# Power_Supply.net
KiCad netlist of a schematic drawn in Altium Designer
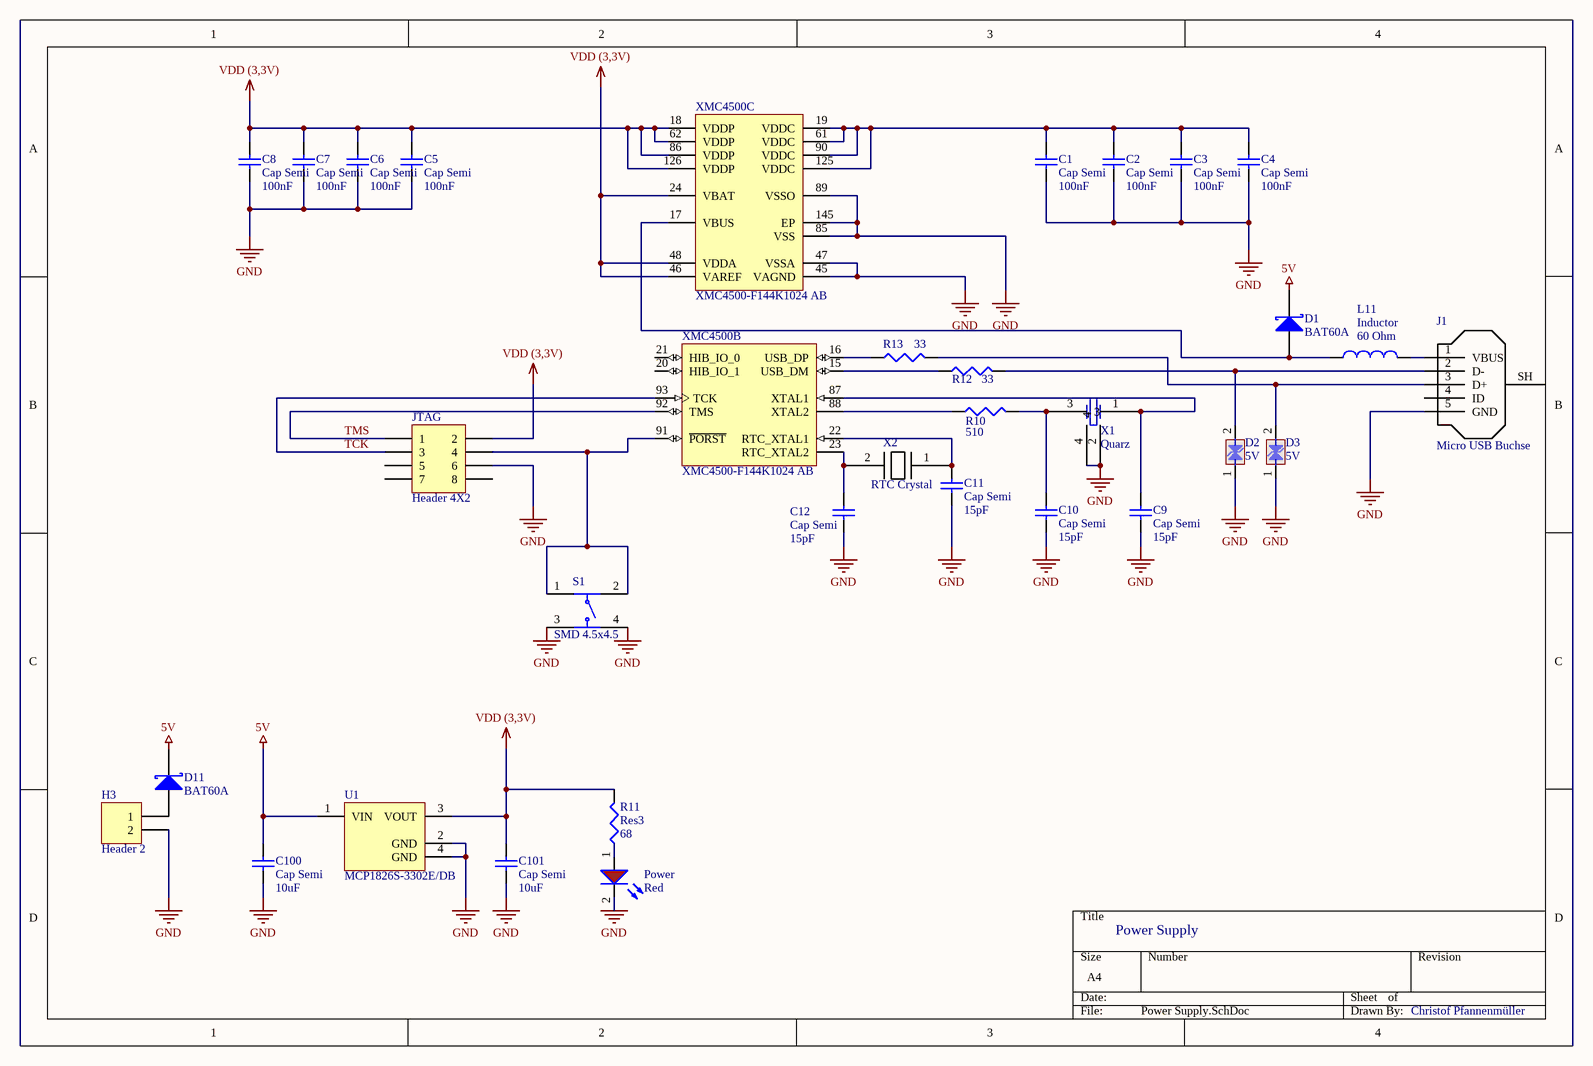
[diagram p0: Power Supply.SchDoc]

(export (version "E")
  (design (tool "Eeschema 10.0.6"))
  (components
    (comp (ref "C1")
      (value "Cap Semi")
      (footprint "0402")
      (description "Capacitor (Semiconductor SIM Model)")
      (fields (field (name "ALTIUM_VALUE") "100nF") (field (name "PUBLISHER") "Altium Limited"))
      (libsource (lib "Miscellaneous Devices") (part "Cap Semi"))
    )
    (comp (ref "C2")
      (value "Cap Semi")
      (footprint "0402")
      (description "Capacitor (Semiconductor SIM Model)")
      (fields (field (name "ALTIUM_VALUE") "100nF") (field (name "PUBLISHER") "Altium Limited"))
      (libsource (lib "Miscellaneous Devices") (part "Cap Semi"))
    )
    (comp (ref "C3")
      (value "Cap Semi")
      (footprint "0402")
      (description "Capacitor (Semiconductor SIM Model)")
      (fields (field (name "ALTIUM_VALUE") "100nF") (field (name "PUBLISHER") "Altium Limited"))
      (libsource (lib "Miscellaneous Devices") (part "Cap Semi"))
    )
    (comp (ref "C4")
      (value "Cap Semi")
      (footprint "0402")
      (description "Capacitor (Semiconductor SIM Model)")
      (fields (field (name "ALTIUM_VALUE") "100nF") (field (name "PUBLISHER") "Altium Limited"))
      (libsource (lib "Miscellaneous Devices") (part "Cap Semi"))
    )
    (comp (ref "C5")
      (value "Cap Semi")
      (footprint "0402")
      (description "Capacitor (Semiconductor SIM Model)")
      (fields (field (name "ALTIUM_VALUE") "100nF") (field (name "PUBLISHER") "Altium Limited"))
      (libsource (lib "Miscellaneous Devices") (part "Cap Semi"))
    )
    (comp (ref "C6")
      (value "Cap Semi")
      (footprint "0402")
      (description "Capacitor (Semiconductor SIM Model)")
      (fields (field (name "ALTIUM_VALUE") "100nF") (field (name "PUBLISHER") "Altium Limited"))
      (libsource (lib "Miscellaneous Devices") (part "Cap Semi"))
    )
    (comp (ref "C7")
      (value "Cap Semi")
      (footprint "0402")
      (description "Capacitor (Semiconductor SIM Model)")
      (fields (field (name "ALTIUM_VALUE") "100nF") (field (name "PUBLISHER") "Altium Limited"))
      (libsource (lib "Miscellaneous Devices") (part "Cap Semi"))
    )
    (comp (ref "C8")
      (value "Cap Semi")
      (footprint "0402")
      (description "Capacitor (Semiconductor SIM Model)")
      (fields (field (name "ALTIUM_VALUE") "100nF") (field (name "PUBLISHER") "Altium Limited"))
      (libsource (lib "Miscellaneous Devices") (part "Cap Semi"))
    )
    (comp (ref "C9")
      (value "Cap Semi")
      (footprint "0402")
      (description "Capacitor (Semiconductor SIM Model)")
      (fields (field (name "ALTIUM_VALUE") "15pF") (field (name "PUBLISHER") "Altium Limited"))
      (libsource (lib "Miscellaneous Devices") (part "Cap Semi"))
    )
    (comp (ref "C10")
      (value "Cap Semi")
      (footprint "0402")
      (description "Capacitor (Semiconductor SIM Model)")
      (fields (field (name "ALTIUM_VALUE") "15pF") (field (name "PUBLISHER") "Altium Limited"))
      (libsource (lib "Miscellaneous Devices") (part "Cap Semi"))
    )
    (comp (ref "C11")
      (value "Cap Semi")
      (footprint "0402")
      (description "Capacitor (Semiconductor SIM Model)")
      (fields (field (name "ALTIUM_VALUE") "15pF") (field (name "PUBLISHER") "Altium Limited"))
      (libsource (lib "Miscellaneous Devices") (part "Cap Semi"))
    )
    (comp (ref "C12")
      (value "Cap Semi")
      (footprint "0402")
      (description "Capacitor (Semiconductor SIM Model)")
      (fields (field (name "ALTIUM_VALUE") "15pF") (field (name "PUBLISHER") "Altium Limited"))
      (libsource (lib "Miscellaneous Devices") (part "Cap Semi"))
    )
    (comp (ref "C100")
      (value "Cap Semi")
      (footprint "C1206")
      (description "Capacitor (Semiconductor SIM Model)")
      (fields (field (name "ALTIUM_VALUE") "10uF") (field (name "PUBLISHER") "Altium Limited"))
      (libsource (lib "Miscellaneous Devices") (part "Cap Semi"))
    )
    (comp (ref "C101")
      (value "Cap Semi")
      (footprint "C1206")
      (description "Capacitor (Semiconductor SIM Model)")
      (fields (field (name "ALTIUM_VALUE") "10uF") (field (name "PUBLISHER") "Altium Limited"))
      (libsource (lib "Miscellaneous Devices") (part "Cap Semi"))
    )
    (comp (ref "D1")
      (value "BAT60A")
      (footprint "SOD-323")
      (description "Silicon AF Schottky Rectifier Diode with Extreme Low VF Drop")
      (fields (field (name "PUBLISHER") "Altium Limited"))
      (libsource (lib "Infineon Discrete Diode") (part "BAT60A"))
    )
    (comp (ref "D2")
      (value "5V")
      (footprint "WE-VE_0603")
      (description "WE-VE ESD Suppressor, 0603, VDC=5V")
      (fields
        (field (name "PARTNO") "82356050560")
        (field (name "MANUFACTURER") "Wurth Elektronik")
        (field (name "CREATED BY") "BJ.Chen")
      )
      (libsource (lib "WE-VE_rev16a") (part "WE-VE 0603, 82356050560"))
    )
    (comp (ref "D3")
      (value "5V")
      (footprint "WE-VE_0603")
      (description "WE-VE ESD Suppressor, 0603, VDC=5V")
      (fields
        (field (name "PARTNO") "82356050560")
        (field (name "MANUFACTURER") "Wurth Elektronik")
        (field (name "CREATED BY") "BJ.Chen")
      )
      (libsource (lib "WE-VE_rev16a") (part "WE-VE 0603, 82356050560"))
    )
    (comp (ref "D11")
      (value "BAT60A")
      (footprint "SOD-323")
      (description "Silicon AF Schottky Rectifier Diode with Extreme Low VF Drop")
      (fields (field (name "PUBLISHER") "Altium Limited"))
      (libsource (lib "Infineon Discrete Diode") (part "BAT60A"))
    )
    (comp (ref "H3")
      (value "Header 2")
      (footprint "HDR1X2")
      (description "Header, 2-Pin")
      (fields (field (name "PUBLISHER") "Altium Limited"))
      (libsource (lib "Miscellaneous Connectors") (part "Header 2"))
    )
    (comp (ref "J1")
      (value "Micro USB Buchse")
      (footprint "Micro USB Buchse - Molex")
      (libsource (lib "Schematic library") (part "Micro USB Buchse - Molex"))
    )
    (comp (ref "JTAG")
      (value "Header 4X2")
      (footprint "HDR2X4")
      (description "Header, 4-Pin, Dual row")
      (fields (field (name "PUBLISHER") "Altium Limited"))
      (libsource (lib "Miscellaneous Connectors") (part "Header 4X2"))
    )
    (comp (ref "L11")
      (value "Inductor")
      (footprint "0603")
      (fields (field (name "ALTIUM_VALUE") "60 Ohm") (field (name "PUBLISHER") "Altium Limited"))
      (libsource (lib "Miscellaneous Devices") (part "Inductor"))
    )
    (comp (ref "Power")
      (value "Red")
      (footprint "LED_0805_Red")
      (description "SMD mono-color Chip LED, WL-SMCW, Red")
      (fields
        (field (name "PARTNO") "150080RS75000")
        (field (name "MANUFACTURER") "W黵th Elektronik eiSos GmbH")
        (field (name "CREATED BY") "Christin Otto")
      )
      (libsource (lib "WL-SMCW_rev15b") (part "WL-SMCW 0805  150080RS75000"))
    )
    (comp (ref "R10")
      (value "510")
      (footprint "J1-0603")
      (description "Resistor")
      (fields (field (name "Comment") "Res3") (field (name "PUBLISHER") "Altium Limited"))
      (libsource (lib "Miscellaneous Devices") (part "Res3"))
    )
    (comp (ref "R11")
      (value "Res3")
      (footprint "J1-0603")
      (description "Resistor")
      (fields (field (name "ALTIUM_VALUE") "68") (field (name "PUBLISHER") "Altium Limited"))
      (libsource (lib "Miscellaneous Devices") (part "Res3"))
    )
    (comp (ref "R12")
      (value "33")
      (footprint "J1-0603")
      (description "Resistor")
      (fields (field (name "Comment") "Res3") (field (name "PUBLISHER") "Altium Limited"))
      (libsource (lib "Miscellaneous Devices") (part "Res3"))
    )
    (comp (ref "R13")
      (value "33")
      (footprint "J1-0603")
      (description "Resistor")
      (fields (field (name "Comment") "Res3") (field (name "PUBLISHER") "Altium Limited"))
      (libsource (lib "Miscellaneous Devices") (part "Res3"))
    )
    (comp (ref "S1")
      (value "SMD 4.5x4.5")
      (footprint "430181038816")
      (description "WS-TASV 4.5x4.5 mm SMD")
      (fields
        (field (name "PARTNO") "430181038816")
        (field (name "MANUFACTURER") "Wurth Elektronik")
        (field (name "CREATED BY") "Baojun Chen")
      )
      (libsource (lib "WS-TASV_rev15a") (part "WS-TASV, 430181038816"))
    )
    (comp (ref "U1")
      (value "MCP1826S-3302E/DB")
      (footprint "SOT-223-DB3_N")
      (description "1000 mA, Low Voltage, Low Quiescent Current LDO Regulator, 3-Pin SOT-223, Extended Temperature")
      (fields (field (name "MANUFACTURER") "Microchip"))
      (libsource (lib "Microchip Power Management Line Regulator") (part "MCP1826S-3302E/DB"))
    )
    (comp (ref "X1") (value "Quarz") (footprint "Quarz") (libsource (lib "Schlib1") (part "Quarz")))
    (comp (ref "X2")
      (value "RTC Crystal")
      (footprint "RTC Uhrenquarz  1.5x3.2 SMD")
      (libsource (lib "Schematic library") (part "RTC Crystal"))
    )
    (comp (ref "XMC4500")
      (value "XMC4500-F144K1024 AB")
      (footprint "INF-PG-LQFP-144-18-6500X6500TP_N")
      (fields (field (name "MANUFACTURER") "Infineon"))
      (libsource (lib "Infineon XMC4000") (part "XMC4500-F144K1024 AB"))
    )
  )
  (nets
    (net (code "1") (name "/TCK") (class "Default")
      (node (ref "JTAG") (pin "3") (pinfunction "3_3") (pintype "passive"))
      (node (ref "XMC4500") (pin "93") (pinfunction "TCK_93") (pintype "input"))
    )
    (net (code "2") (name "/TMS") (class "Default")
      (node (ref "JTAG") (pin "1") (pinfunction "1_1") (pintype "passive"))
      (node (ref "XMC4500") (pin "92") (pinfunction "TMS_92") (pintype "bidirectional"))
    )
    (net (code "3") (name "5V") (class "Default")
      (node (ref "C100") (pin "2") (pinfunction "2_2") (pintype "passive"))
      (node (ref "D1") (pin "1") (pinfunction "K_1") (pintype "passive"))
      (node (ref "D11") (pin "1") (pinfunction "K_1") (pintype "passive"))
      (node (ref "U1") (pin "1") (pinfunction "VIN_1") (pintype "power_in"))
    )
    (net (code "4") (name "GND") (class "Default")
      (node (ref "C1") (pin "1") (pinfunction "1_1") (pintype "passive"))
      (node (ref "C10") (pin "1") (pinfunction "1_1") (pintype "passive"))
      (node (ref "C100") (pin "1") (pinfunction "1_1") (pintype "passive"))
      (node (ref "C101") (pin "1") (pinfunction "1_1") (pintype "passive"))
      (node (ref "C11") (pin "1") (pinfunction "1_1") (pintype "passive"))
      (node (ref "C12") (pin "1") (pinfunction "1_1") (pintype "passive"))
      (node (ref "C2") (pin "1") (pinfunction "1_1") (pintype "passive"))
      (node (ref "C3") (pin "1") (pinfunction "1_1") (pintype "passive"))
      (node (ref "C4") (pin "1") (pinfunction "1_1") (pintype "passive"))
      (node (ref "C5") (pin "1") (pinfunction "1_1") (pintype "passive"))
      (node (ref "C6") (pin "1") (pinfunction "1_1") (pintype "passive"))
      (node (ref "C7") (pin "1") (pinfunction "1_1") (pintype "passive"))
      (node (ref "C8") (pin "1") (pinfunction "1_1") (pintype "passive"))
      (node (ref "C9") (pin "1") (pinfunction "1_1") (pintype "passive"))
      (node (ref "D2") (pin "1") (pinfunction "I/O1_1") (pintype "passive"))
      (node (ref "D3") (pin "1") (pinfunction "I/O1_1") (pintype "passive"))
      (node (ref "H3") (pin "2") (pinfunction "2_2") (pintype "passive"))
      (node (ref "J1") (pin "5") (pinfunction "GND_5") (pintype "passive"))
      (node (ref "JTAG") (pin "6") (pinfunction "6_6") (pintype "passive"))
      (node (ref "Power") (pin "2") (pinfunction "C_2") (pintype "passive"))
      (node (ref "S1") (pin "3") (pinfunction "3_3") (pintype "passive"))
      (node (ref "S1") (pin "4") (pinfunction "4_4") (pintype "passive"))
      (node (ref "U1") (pin "2") (pinfunction "GND_2") (pintype "power_in"))
      (node (ref "U1") (pin "4") (pinfunction "GND_4") (pintype "power_in"))
      (node (ref "X1") (pin "2") (pinfunction "2_2") (pintype "passive"))
      (node (ref "X1") (pin "4") (pinfunction "4_4") (pintype "passive"))
      (node (ref "XMC4500") (pin "145") (pinfunction "EP_145") (pintype "power_in"))
      (node (ref "XMC4500") (pin "45") (pinfunction "VAGND_45") (pintype "power_in"))
      (node (ref "XMC4500") (pin "47") (pinfunction "VSSA_47") (pintype "power_in"))
      (node (ref "XMC4500") (pin "85") (pinfunction "VSS_85") (pintype "power_in"))
      (node (ref "XMC4500") (pin "89") (pinfunction "VSSO_89") (pintype "power_in"))
    )
    (net (code "5") (name "Net-(C1-Pad2)") (class "Default")
      (node (ref "C1") (pin "2") (pinfunction "2_2") (pintype "passive"))
      (node (ref "C2") (pin "2") (pinfunction "2_2") (pintype "passive"))
      (node (ref "C3") (pin "2") (pinfunction "2_2") (pintype "passive"))
      (node (ref "C4") (pin "2") (pinfunction "2_2") (pintype "passive"))
      (node (ref "XMC4500") (pin "125") (pinfunction "VDDC_125") (pintype "power_in"))
      (node (ref "XMC4500") (pin "19") (pinfunction "VDDC_19") (pintype "power_in"))
      (node (ref "XMC4500") (pin "61") (pinfunction "VDDC_61") (pintype "power_in"))
      (node (ref "XMC4500") (pin "90") (pinfunction "VDDC_90") (pintype "power_in"))
    )
    (net (code "6") (name "Net-(C10-Pad2)") (class "Default")
      (node (ref "C10") (pin "2") (pinfunction "2_2") (pintype "passive"))
      (node (ref "R10") (pin "2") (pinfunction "2_2") (pintype "passive"))
      (node (ref "X1") (pin "3") (pinfunction "3_3") (pintype "passive"))
    )
    (net (code "7") (name "Net-(D1-A)") (class "Default")
      (node (ref "D1") (pin "2") (pinfunction "A_2") (pintype "passive"))
      (node (ref "L11") (pin "1") (pinfunction "1_1") (pintype "passive"))
      (node (ref "XMC4500") (pin "17") (pinfunction "VBUS_17") (pintype "power_in"))
    )
    (net (code "8") (name "Net-(D2-I{slash}O2)") (class "Default")
      (node (ref "D2") (pin "2") (pinfunction "I/O2_2") (pintype "passive"))
      (node (ref "J1") (pin "2") (pinfunction "D-_2") (pintype "passive"))
      (node (ref "R12") (pin "2") (pinfunction "2_2") (pintype "passive"))
    )
    (net (code "9") (name "Net-(D3-I{slash}O2)") (class "Default")
      (node (ref "D3") (pin "2") (pinfunction "I/O2_2") (pintype "passive"))
      (node (ref "J1") (pin "3") (pinfunction "D+_3") (pintype "passive"))
      (node (ref "R13") (pin "2") (pinfunction "2_2") (pintype "passive"))
    )
    (net (code "10") (name "Net-(D11-A)") (class "Default")
      (node (ref "D11") (pin "2") (pinfunction "A_2") (pintype "passive"))
      (node (ref "H3") (pin "1") (pinfunction "1_1") (pintype "passive"))
    )
    (net (code "11") (name "Net-(J1-VBUS)") (class "Default")
      (node (ref "J1") (pin "1") (pinfunction "VBUS_1") (pintype "passive"))
      (node (ref "L11") (pin "2") (pinfunction "2_2") (pintype "passive"))
    )
    (net (code "12") (name "Net-(Power-A)") (class "Default")
      (node (ref "Power") (pin "1") (pinfunction "A_1") (pintype "passive"))
      (node (ref "R11") (pin "1") (pinfunction "1_1") (pintype "passive"))
    )
    (net (code "13") (name "Net-(XMC4500B-RTC_XTAL1)") (class "Default")
      (node (ref "C11") (pin "2") (pinfunction "2_2") (pintype "passive"))
      (node (ref "X2") (pin "1") (pintype "passive"))
      (node (ref "XMC4500") (pin "22") (pinfunction "RTC_XTAL1_22") (pintype "input"))
    )
    (net (code "14") (name "Net-(XMC4500B-RTC_XTAL2)") (class "Default")
      (node (ref "C12") (pin "2") (pinfunction "2_2") (pintype "passive"))
      (node (ref "X2") (pin "2") (pintype "passive"))
      (node (ref "XMC4500") (pin "23") (pinfunction "RTC_XTAL2_23") (pintype "passive"))
    )
    (net (code "15") (name "Net-(XMC4500B-USB_DM)") (class "Default")
      (node (ref "R12") (pin "1") (pinfunction "1_1") (pintype "passive"))
      (node (ref "XMC4500") (pin "15") (pinfunction "USB_DM_15") (pintype "bidirectional"))
    )
    (net (code "16") (name "Net-(XMC4500B-USB_DP)") (class "Default")
      (node (ref "R13") (pin "1") (pinfunction "1_1") (pintype "passive"))
      (node (ref "XMC4500") (pin "16") (pinfunction "USB_DP_16") (pintype "bidirectional"))
    )
    (net (code "17") (name "Net-(XMC4500B-XTAL1)") (class "Default")
      (node (ref "C9") (pin "2") (pinfunction "2_2") (pintype "passive"))
      (node (ref "X1") (pin "1") (pinfunction "1_1") (pintype "passive"))
      (node (ref "XMC4500") (pin "87") (pinfunction "XTAL1_87") (pintype "input"))
    )
    (net (code "18") (name "Net-(XMC4500B-XTAL2)") (class "Default")
      (node (ref "R10") (pin "1") (pinfunction "1_1") (pintype "passive"))
      (node (ref "XMC4500") (pin "88") (pinfunction "XTAL2_88") (pintype "passive"))
    )
    (net (code "19") (name "Net-(XMC4500B-~{PORST})") (class "Default")
      (node (ref "JTAG") (pin "4") (pinfunction "4_4") (pintype "passive"))
      (node (ref "S1") (pin "1") (pinfunction "1_1") (pintype "passive"))
      (node (ref "S1") (pin "2") (pinfunction "2_2") (pintype "passive"))
      (node (ref "XMC4500") (pin "91") (pinfunction "~{PORST}_91") (pintype "bidirectional"))
    )
    (net (code "20") (name "VDD (3,3V)") (class "Default")
      (node (ref "C101") (pin "2") (pinfunction "2_2") (pintype "passive"))
      (node (ref "C5") (pin "2") (pinfunction "2_2") (pintype "passive"))
      (node (ref "C6") (pin "2") (pinfunction "2_2") (pintype "passive"))
      (node (ref "C7") (pin "2") (pinfunction "2_2") (pintype "passive"))
      (node (ref "C8") (pin "2") (pinfunction "2_2") (pintype "passive"))
      (node (ref "JTAG") (pin "2") (pinfunction "2_2") (pintype "passive"))
      (node (ref "R11") (pin "2") (pinfunction "2_2") (pintype "passive"))
      (node (ref "U1") (pin "3") (pinfunction "VOUT_3") (pintype "power_in"))
      (node (ref "XMC4500") (pin "126") (pinfunction "VDDP_126") (pintype "power_in"))
      (node (ref "XMC4500") (pin "18") (pinfunction "VDDP_18") (pintype "power_in"))
      (node (ref "XMC4500") (pin "24") (pinfunction "VBAT_24") (pintype "power_in"))
      (node (ref "XMC4500") (pin "46") (pinfunction "VAREF_46") (pintype "power_in"))
      (node (ref "XMC4500") (pin "48") (pinfunction "VDDA_48") (pintype "power_in"))
      (node (ref "XMC4500") (pin "62") (pinfunction "VDDP_62") (pintype "power_in"))
      (node (ref "XMC4500") (pin "86") (pinfunction "VDDP_86") (pintype "power_in"))
    )
    (net (code "21") (name "unconnected-(J1-ID-Pad4)") (class "Default")
      (node (ref "J1") (pin "4") (pinfunction "ID_4") (pintype "passive"))
    )
    (net (code "22") (name "unconnected-(J1-PadSH)") (class "Default")
      (node (ref "J1") (pin "SH") (pintype "passive"))
    )
    (net (code "23") (name "unconnected-(JTAG-Pad5)") (class "Default")
      (node (ref "JTAG") (pin "5") (pinfunction "5_5") (pintype "passive"))
    )
    (net (code "24") (name "unconnected-(JTAG-Pad7)") (class "Default")
      (node (ref "JTAG") (pin "7") (pinfunction "7_7") (pintype "passive"))
    )
    (net (code "25") (name "unconnected-(JTAG-Pad8)") (class "Default")
      (node (ref "JTAG") (pin "8") (pinfunction "8_8") (pintype "passive"))
    )
    (net (code "26") (name "unconnected-(XMC4500B-HIB_IO_0-Pad21)") (class "Default")
      (node (ref "XMC4500") (pin "21") (pinfunction "HIB_IO_0_21") (pintype "bidirectional"))
    )
    (net (code "27") (name "unconnected-(XMC4500B-HIB_IO_1-Pad20)") (class "Default")
      (node (ref "XMC4500") (pin "20") (pinfunction "HIB_IO_1_20") (pintype "bidirectional"))
    )
  )
)
